# STM32G431CBT6.net
KiCad netlist of a schematic drawn in Altium Designer
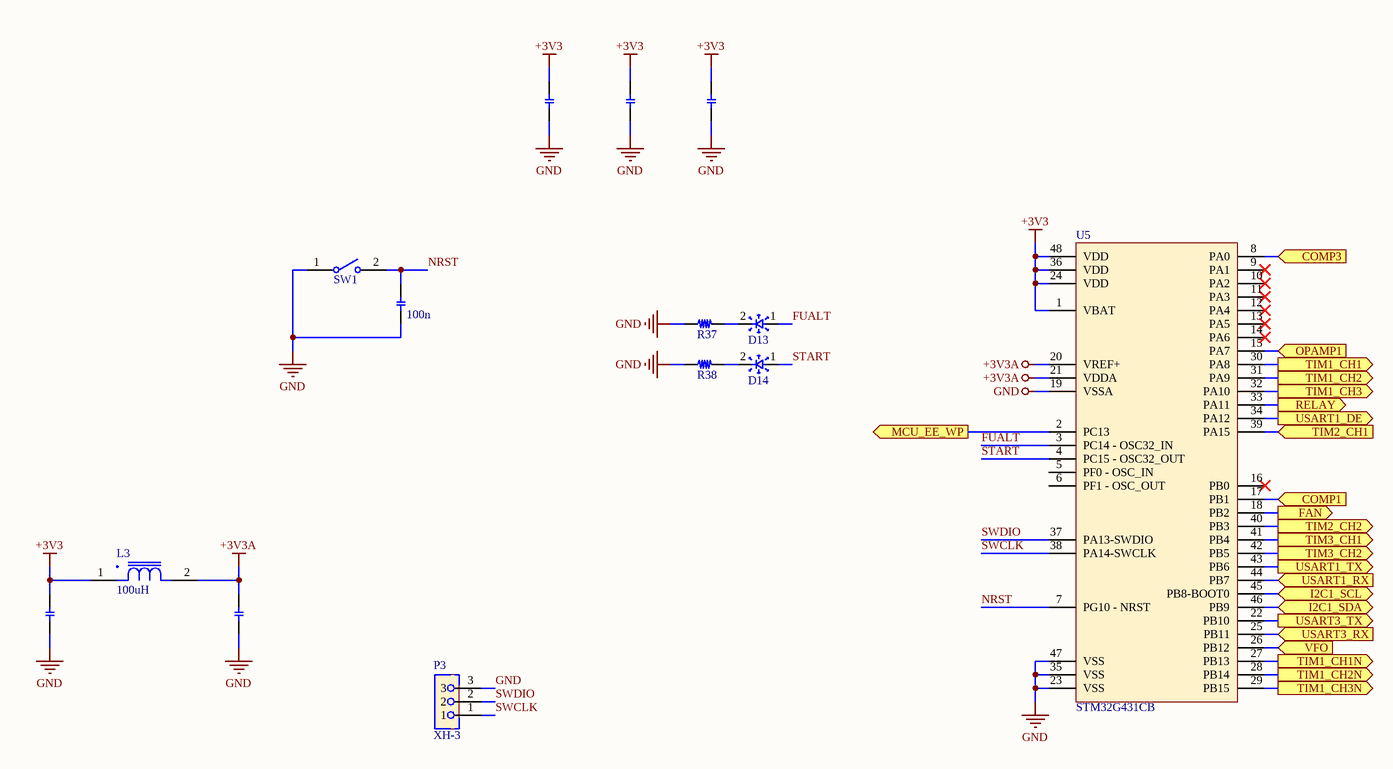
[diagram p0: STM32G431CBT6.SchDoc]

(export (version "E")
  (design (tool "Eeschema 10.0.6"))
  (components
    (comp (ref "C40")
      (value "CAP_SMD")
      (footprint "C 0603")
      (libsource (lib "radmehr_library") (part "CAP_SMD"))
    )
    (comp (ref "C41")
      (value "CAP_SMD")
      (footprint "C 0603")
      (libsource (lib "radmehr_library") (part "CAP_SMD"))
    )
    (comp (ref "C42")
      (value "CAP_SMD")
      (footprint "C 0603")
      (libsource (lib "radmehr_library") (part "CAP_SMD"))
    )
    (comp (ref "C43")
      (value "100n")
      (footprint "C 0603")
      (description "CAP_SMD")
      (libsource (lib "radmehr_library") (part "CAP_SMD"))
    )
    (comp (ref "C44")
      (value "CAP_SMD")
      (footprint "C 0603")
      (libsource (lib "radmehr_library") (part "CAP_SMD"))
    )
    (comp (ref "C45")
      (value "CAP_SMD")
      (footprint "C 0603")
      (libsource (lib "radmehr_library") (part "CAP_SMD"))
    )
    (comp (ref "D13")
      (value "LED_SMD")
      (footprint "D 0603")
      (libsource (lib "radmehr_library") (part "LED_SMD"))
    )
    (comp (ref "D14")
      (value "LED_SMD")
      (footprint "D 0603")
      (libsource (lib "radmehr_library") (part "LED_SMD"))
    )
    (comp (ref "L3")
      (value "100uH")
      (footprint "L 0805")
      (description "Inductor")
      (libsource (lib "radmehr_library") (part "Inductor"))
    )
    (comp (ref "P3") (value "XH-3") (footprint "XH-3") (libsource (lib "radmehr_library") (part "XH-3")))
    (comp (ref "R37")
      (value "RES_SMD")
      (footprint "R 0603")
      (libsource (lib "radmehr_library") (part "RES_SMD"))
    )
    (comp (ref "R38")
      (value "RES_SMD")
      (footprint "R 0603")
      (libsource (lib "radmehr_library") (part "RES_SMD"))
    )
    (comp (ref "SW1")
      (value "434121043836")
      (footprint "WS-TASV_L6W3.5H4.3_4341x10438x6")
      (description "WS-TASV SMT Tact Switch, L6 x W3.5 x H4.3mm, 360g, SPST-NO, 12V, 50mA")
      (fields (field (name "MANUFACTURER") "Wurth Elektronik"))
      (libsource (lib "Altium_WS-TASV (rev22c) (1)") (part "434121043836"))
    )
    (comp (ref "U5")
      (value "STM32G431CB")
      (footprint "QFP-48")
      (libsource (lib "radmehr_library") (part "STM32G431CB"))
    )
  )
  (nets
    (net (code "1") (name "+3V3") (class "Default")
      (node (ref "C40") (pin "2") (pinfunction "2_2") (pintype "passive"))
      (node (ref "C41") (pin "2") (pinfunction "2_2") (pintype "passive"))
      (node (ref "C42") (pin "2") (pinfunction "2_2") (pintype "passive"))
      (node (ref "C44") (pin "2") (pinfunction "2_2") (pintype "passive"))
      (node (ref "L3") (pin "1") (pintype "passive"))
      (node (ref "U5") (pin "1") (pinfunction "VBAT_1") (pintype "passive"))
      (node (ref "U5") (pin "24") (pinfunction "VDD_24") (pintype "passive"))
      (node (ref "U5") (pin "36") (pinfunction "VDD_36") (pintype "passive"))
      (node (ref "U5") (pin "48") (pinfunction "VDD_48") (pintype "passive"))
    )
    (net (code "2") (name "+3V3A") (class "Default")
      (node (ref "C45") (pin "2") (pinfunction "2_2") (pintype "passive"))
      (node (ref "L3") (pin "2") (pintype "passive"))
      (node (ref "U5") (pin "20") (pinfunction "VREF+_20") (pintype "passive"))
      (node (ref "U5") (pin "21") (pinfunction "VDDA_21") (pintype "passive"))
    )
    (net (code "3") (name "/COMP1") (class "Default")
      (node (ref "U5") (pin "17") (pinfunction "PB1_17") (pintype "passive"))
    )
    (net (code "4") (name "/COMP3") (class "Default")
      (node (ref "U5") (pin "8") (pinfunction "PA0_8") (pintype "passive"))
    )
    (net (code "5") (name "/FAN") (class "Default")
      (node (ref "U5") (pin "18") (pinfunction "PB2_18") (pintype "passive"))
    )
    (net (code "6") (name "/FUALT") (class "Default")
      (node (ref "D13") (pin "1") (pintype "passive"))
      (node (ref "U5") (pin "3") (pinfunction "PC14_-_OSC32_IN_3") (pintype "passive"))
    )
    (net (code "7") (name "/I2C1_SCL") (class "Default")
      (node (ref "U5") (pin "45") (pinfunction "PB8-BOOT0_45") (pintype "passive"))
    )
    (net (code "8") (name "/I2C1_SDA") (class "Default")
      (node (ref "U5") (pin "46") (pinfunction "PB9_46") (pintype "passive"))
    )
    (net (code "9") (name "/MCU_EE_WP") (class "Default")
      (node (ref "U5") (pin "2") (pinfunction "PC13_2") (pintype "passive"))
    )
    (net (code "10") (name "/NRST") (class "Default")
      (node (ref "C43") (pin "2") (pinfunction "2_2") (pintype "passive"))
      (node (ref "SW1") (pin "2") (pinfunction "2_2") (pintype "passive"))
      (node (ref "U5") (pin "7") (pinfunction "PG10_-_NRST_7") (pintype "passive"))
    )
    (net (code "11") (name "/OPAMP1") (class "Default")
      (node (ref "U5") (pin "15") (pinfunction "PA7_15") (pintype "passive"))
    )
    (net (code "12") (name "/RELAY") (class "Default")
      (node (ref "U5") (pin "33") (pinfunction "PA11_33") (pintype "passive"))
    )
    (net (code "13") (name "/START") (class "Default")
      (node (ref "D14") (pin "1") (pintype "passive"))
      (node (ref "U5") (pin "4") (pinfunction "PC15_-_OSC32_OUT_4") (pintype "passive"))
    )
    (net (code "14") (name "/SWCLK") (class "Default")
      (node (ref "P3") (pin "1") (pinfunction "1_1") (pintype "passive"))
      (node (ref "U5") (pin "38") (pinfunction "PA14-SWCLK_38") (pintype "passive"))
    )
    (net (code "15") (name "/SWDIO") (class "Default")
      (node (ref "P3") (pin "2") (pinfunction "2_2") (pintype "passive"))
      (node (ref "U5") (pin "37") (pinfunction "PA13-SWDIO_37") (pintype "passive"))
    )
    (net (code "16") (name "/TIM1_CH1") (class "Default")
      (node (ref "U5") (pin "30") (pinfunction "PA8_30") (pintype "passive"))
    )
    (net (code "17") (name "/TIM1_CH1N") (class "Default")
      (node (ref "U5") (pin "27") (pinfunction "PB13_27") (pintype "passive"))
    )
    (net (code "18") (name "/TIM1_CH2") (class "Default")
      (node (ref "U5") (pin "31") (pinfunction "PA9_31") (pintype "passive"))
    )
    (net (code "19") (name "/TIM1_CH2N") (class "Default")
      (node (ref "U5") (pin "28") (pinfunction "PB14_28") (pintype "passive"))
    )
    (net (code "20") (name "/TIM1_CH3") (class "Default")
      (node (ref "U5") (pin "32") (pinfunction "PA10_32") (pintype "passive"))
    )
    (net (code "21") (name "/TIM1_CH3N") (class "Default")
      (node (ref "U5") (pin "29") (pinfunction "PB15_29") (pintype "passive"))
    )
    (net (code "22") (name "/TIM2_CH1") (class "Default")
      (node (ref "U5") (pin "39") (pinfunction "PA15_39") (pintype "passive"))
    )
    (net (code "23") (name "/TIM2_CH2") (class "Default")
      (node (ref "U5") (pin "40") (pinfunction "PB3_40") (pintype "passive"))
    )
    (net (code "24") (name "/TIM3_CH1") (class "Default")
      (node (ref "U5") (pin "41") (pinfunction "PB4_41") (pintype "passive"))
    )
    (net (code "25") (name "/TIM3_CH2") (class "Default")
      (node (ref "U5") (pin "42") (pinfunction "PB5_42") (pintype "passive"))
    )
    (net (code "26") (name "/USART1_DE") (class "Default")
      (node (ref "U5") (pin "34") (pinfunction "PA12_34") (pintype "passive"))
    )
    (net (code "27") (name "/USART1_RX") (class "Default")
      (node (ref "U5") (pin "44") (pinfunction "PB7_44") (pintype "passive"))
    )
    (net (code "28") (name "/USART1_TX") (class "Default")
      (node (ref "U5") (pin "43") (pinfunction "PB6_43") (pintype "passive"))
    )
    (net (code "29") (name "/USART3_RX") (class "Default")
      (node (ref "U5") (pin "25") (pinfunction "PB11_25") (pintype "passive"))
    )
    (net (code "30") (name "/USART3_TX") (class "Default")
      (node (ref "U5") (pin "22") (pinfunction "PB10_22") (pintype "passive"))
    )
    (net (code "31") (name "/VFO") (class "Default")
      (node (ref "U5") (pin "26") (pinfunction "PB12_26") (pintype "passive"))
    )
    (net (code "32") (name "GND") (class "Default")
      (node (ref "C40") (pin "1") (pinfunction "1_1") (pintype "passive"))
      (node (ref "C41") (pin "1") (pinfunction "1_1") (pintype "passive"))
      (node (ref "C42") (pin "1") (pinfunction "1_1") (pintype "passive"))
      (node (ref "C43") (pin "1") (pinfunction "1_1") (pintype "passive"))
      (node (ref "C44") (pin "1") (pinfunction "1_1") (pintype "passive"))
      (node (ref "C45") (pin "1") (pinfunction "1_1") (pintype "passive"))
      (node (ref "P3") (pin "3") (pinfunction "3_3") (pintype "passive"))
      (node (ref "R37") (pin "1") (pinfunction "1_1") (pintype "passive"))
      (node (ref "R38") (pin "1") (pinfunction "1_1") (pintype "passive"))
      (node (ref "SW1") (pin "1") (pinfunction "1_1") (pintype "passive"))
      (node (ref "U5") (pin "19") (pinfunction "VSSA_19") (pintype "passive"))
      (node (ref "U5") (pin "23") (pinfunction "VSS_23") (pintype "passive"))
      (node (ref "U5") (pin "35") (pinfunction "VSS_35") (pintype "passive"))
      (node (ref "U5") (pin "47") (pinfunction "VSS_47") (pintype "passive"))
    )
    (net (code "33") (name "Net-(D13-Pad2)") (class "Default")
      (node (ref "D13") (pin "2") (pintype "passive"))
      (node (ref "R37") (pin "2") (pinfunction "2_2") (pintype "passive"))
    )
    (net (code "34") (name "Net-(D14-Pad2)") (class "Default")
      (node (ref "D14") (pin "2") (pintype "passive"))
      (node (ref "R38") (pin "2") (pinfunction "2_2") (pintype "passive"))
    )
    (net (code "35") (name "unconnected-(U5-PA1-Pad9)") (class "Default")
      (node (ref "U5") (pin "9") (pinfunction "PA1_9") (pintype "passive+no_connect"))
    )
    (net (code "36") (name "unconnected-(U5-PA2-Pad10)") (class "Default")
      (node (ref "U5") (pin "10") (pinfunction "PA2_10") (pintype "passive+no_connect"))
    )
    (net (code "37") (name "unconnected-(U5-PA3-Pad11)") (class "Default")
      (node (ref "U5") (pin "11") (pinfunction "PA3_11") (pintype "passive+no_connect"))
    )
    (net (code "38") (name "unconnected-(U5-PA4-Pad12)") (class "Default")
      (node (ref "U5") (pin "12") (pinfunction "PA4_12") (pintype "passive+no_connect"))
    )
    (net (code "39") (name "unconnected-(U5-PA5-Pad13)") (class "Default")
      (node (ref "U5") (pin "13") (pinfunction "PA5_13") (pintype "passive+no_connect"))
    )
    (net (code "40") (name "unconnected-(U5-PA6-Pad14)") (class "Default")
      (node (ref "U5") (pin "14") (pinfunction "PA6_14") (pintype "passive+no_connect"))
    )
    (net (code "41") (name "unconnected-(U5-PB0-Pad16)") (class "Default")
      (node (ref "U5") (pin "16") (pinfunction "PB0_16") (pintype "passive+no_connect"))
    )
    (net (code "42") (name "unconnected-(U5-PF0_-_OSC_IN-Pad5)") (class "Default")
      (node (ref "U5") (pin "5") (pinfunction "PF0_-_OSC_IN_5") (pintype "passive"))
    )
    (net (code "43") (name "unconnected-(U5-PF1_-_OSC_OUT-Pad6)") (class "Default")
      (node (ref "U5") (pin "6") (pinfunction "PF1_-_OSC_OUT_6") (pintype "passive"))
    )
  )
)
